# Smarttree_BMS_6.net
KiCad netlist of a schematic drawn in EAGLE
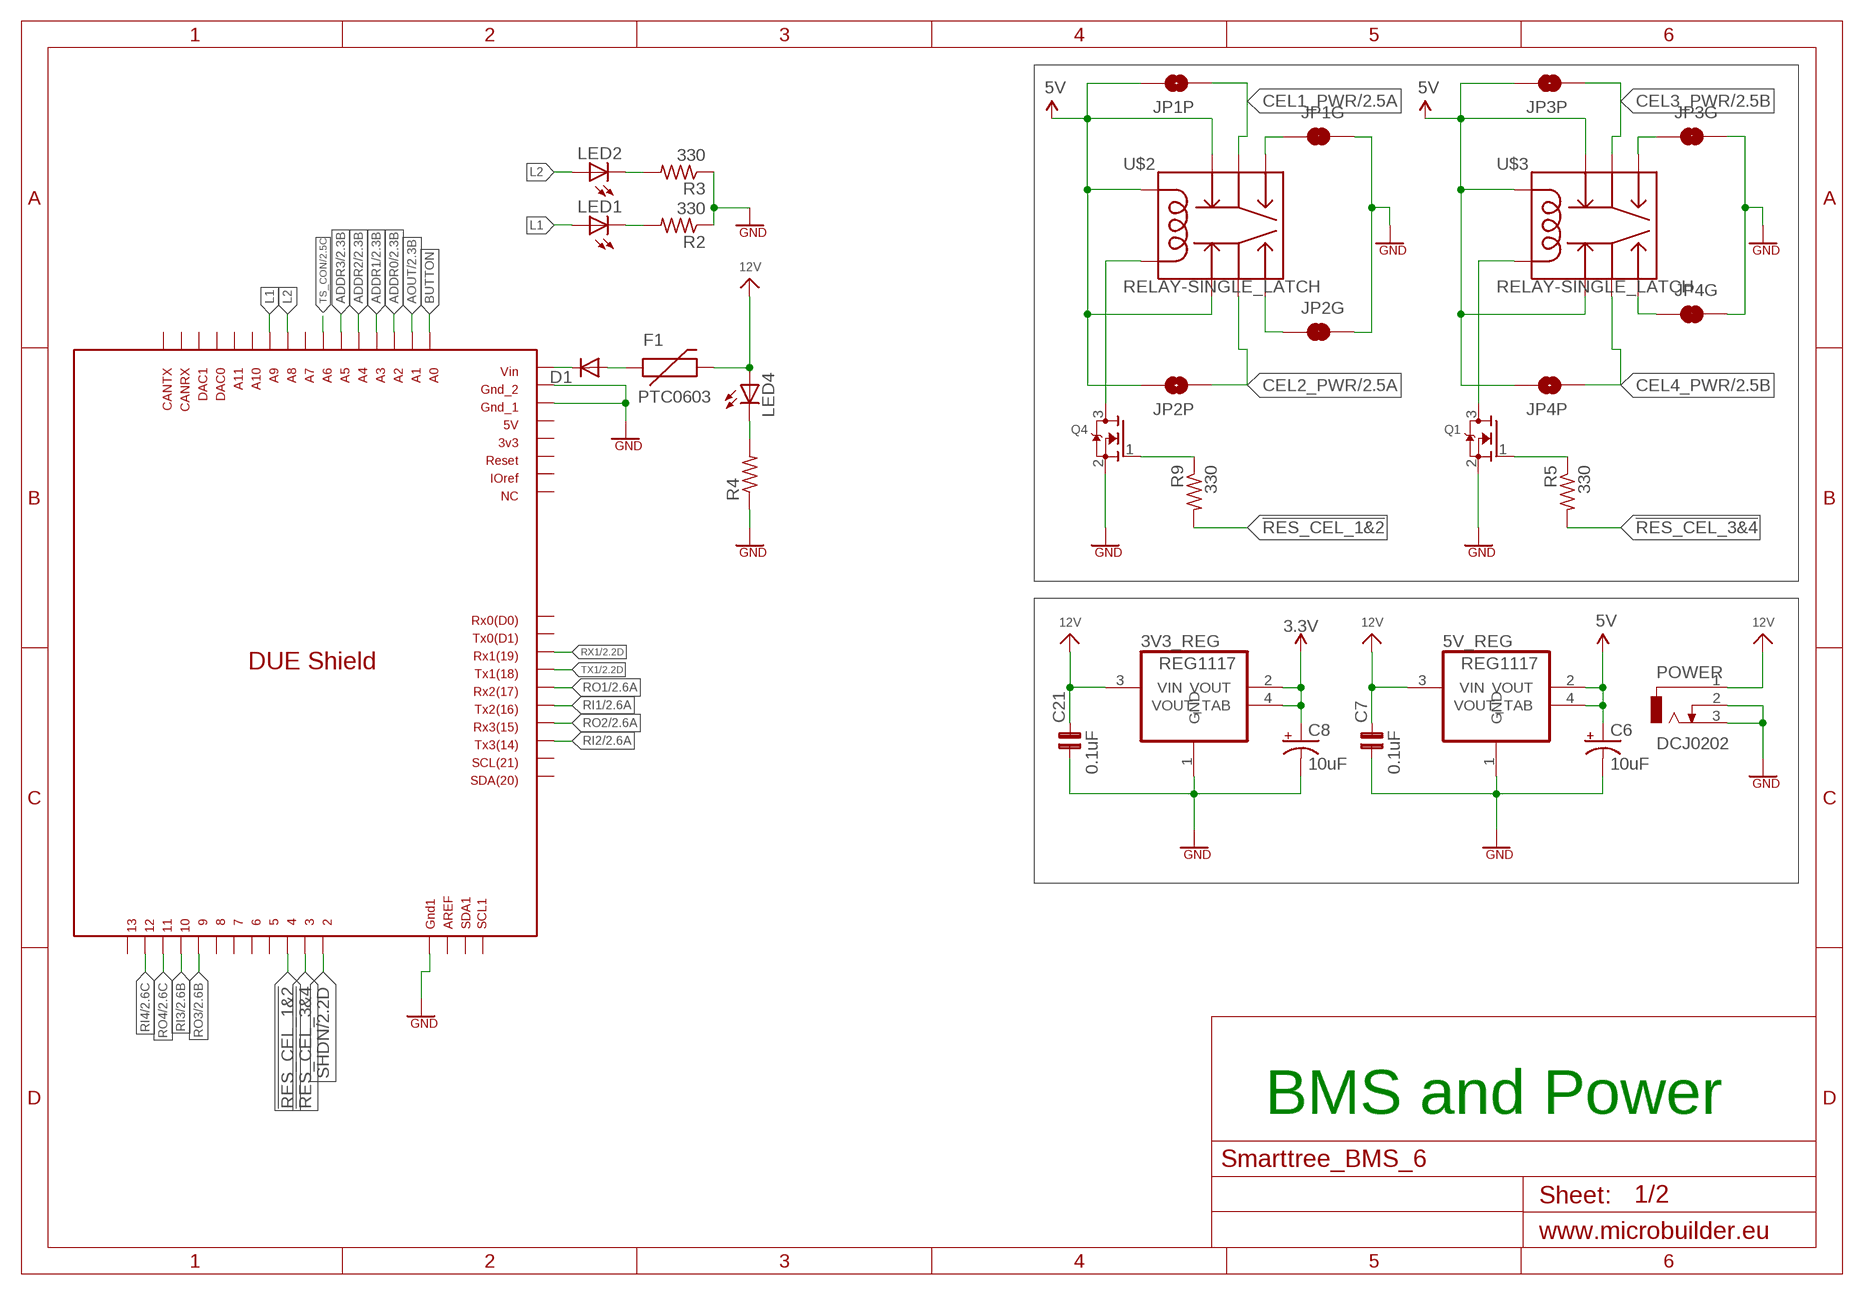
[diagram p0: schematic, sheet 1]
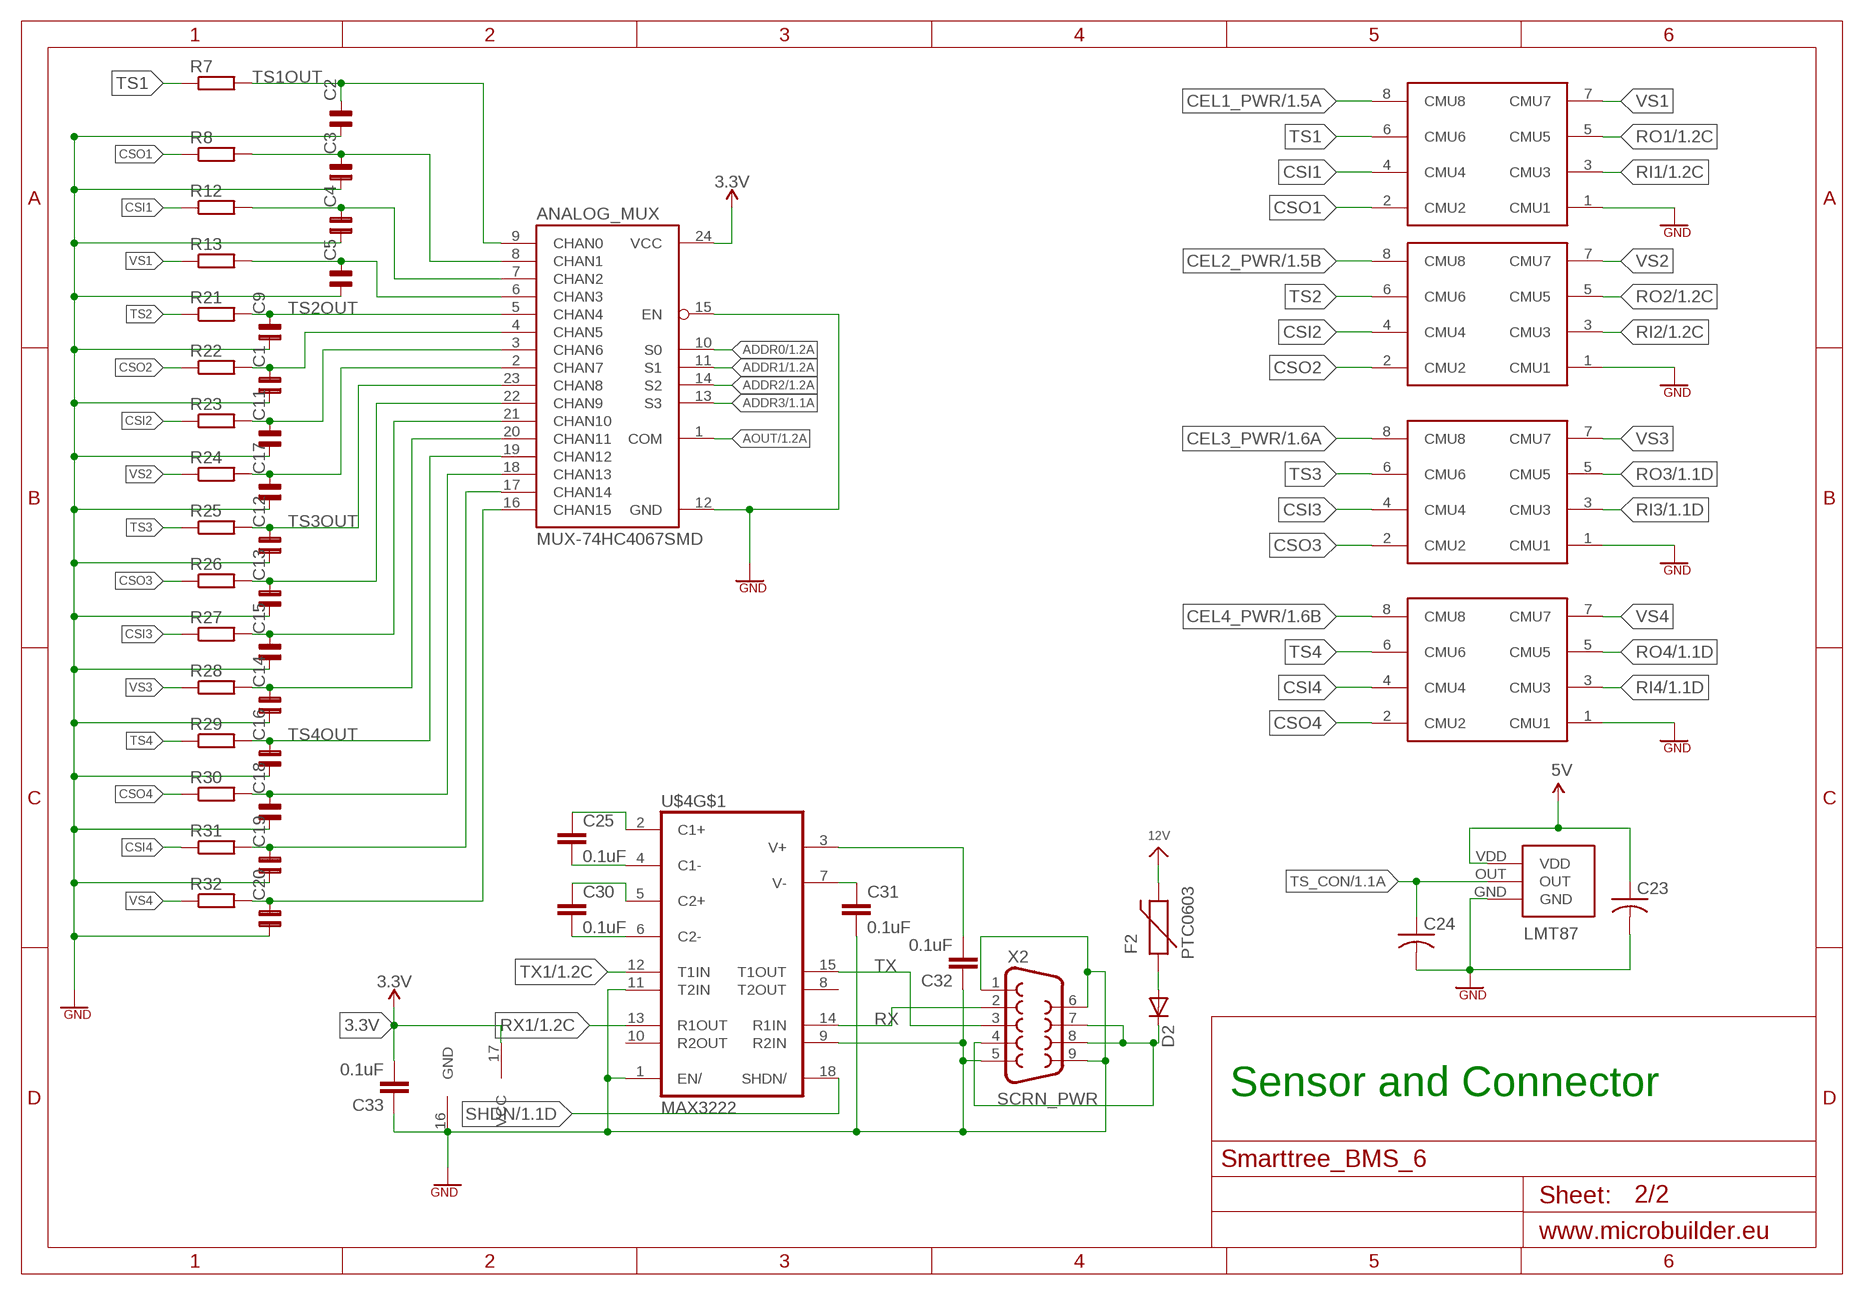
[diagram p1: schematic, sheet 2]

(export (version "E")
  (design (tool "Eeschema 10.0.6"))
  (components
    (comp (ref "3V3_REG")
      (value "REG1117")
      (footprint "eagle-import:SOT223")
      (libsource (lib "eagle-import") (part "REG1117"))
    )
    (comp (ref "5V_REG")
      (value "REG1117")
      (footprint "eagle-import:SOT223")
      (libsource (lib "eagle-import") (part "REG1117"))
    )
    (comp (ref "C6")
      (value "10uF")
      (footprint "eagle-import:EIA3216")
      (libsource (lib "eagle-import") (part "10UF-TANT"))
    )
    (comp (ref "C7")
      (value "0.1uF")
      (footprint "eagle-import:C-0805")
      (libsource (lib "eagle-import") (part "C-NP-SMD-0805"))
    )
    (comp (ref "C8")
      (value "10uF")
      (footprint "eagle-import:EIA3216")
      (libsource (lib "eagle-import") (part "10UF-TANT"))
    )
    (comp (ref "C21")
      (value "0.1uF")
      (footprint "eagle-import:C-0805")
      (libsource (lib "eagle-import") (part "C-NP-SMD-0805"))
    )
    (comp (ref "D1")
      (value "DIODE-SOD106-R")
      (footprint "eagle-import:SOD106-R")
      (libsource (lib "eagle-import") (part "DIODE-SOD106-R"))
    )
    (comp (ref "F1")
      (value "PTC0603")
      (footprint "eagle-import:0603")
      (libsource (lib "eagle-import") (part "PTC0603"))
    )
    (comp (ref "JP1G")
      (value "JUMPER-SMT_2_NC_TRACE_SILK")
      (footprint "eagle-import:SMT-JUMPER_2_NC_TRACE_SILK")
      (libsource (lib "eagle-import") (part "JUMPER-SMT_2_NC_TRACE_SILK"))
    )
    (comp (ref "JP1P")
      (value "JUMPER-SMT_2_NO_SILK")
      (footprint "eagle-import:SMT-JUMPER_2_NO_SILK")
      (libsource (lib "eagle-import") (part "JUMPER-SMT_2_NO_SILK"))
    )
    (comp (ref "JP2G")
      (value "JUMPER-SMT_2_NC_TRACE_SILK")
      (footprint "eagle-import:SMT-JUMPER_2_NC_TRACE_SILK")
      (libsource (lib "eagle-import") (part "JUMPER-SMT_2_NC_TRACE_SILK"))
    )
    (comp (ref "JP2P")
      (value "JUMPER-SMT_2_NO_SILK")
      (footprint "eagle-import:SMT-JUMPER_2_NO_SILK")
      (libsource (lib "eagle-import") (part "JUMPER-SMT_2_NO_SILK"))
    )
    (comp (ref "JP3G")
      (value "JUMPER-SMT_2_NC_TRACE_SILK")
      (footprint "eagle-import:SMT-JUMPER_2_NC_TRACE_SILK")
      (libsource (lib "eagle-import") (part "JUMPER-SMT_2_NC_TRACE_SILK"))
    )
    (comp (ref "JP3P")
      (value "JUMPER-SMT_2_NO_SILK")
      (footprint "eagle-import:SMT-JUMPER_2_NO_SILK")
      (libsource (lib "eagle-import") (part "JUMPER-SMT_2_NO_SILK"))
    )
    (comp (ref "JP4G")
      (value "JUMPER-SMT_2_NC_TRACE_SILK")
      (footprint "eagle-import:SMT-JUMPER_2_NC_TRACE_SILK")
      (libsource (lib "eagle-import") (part "JUMPER-SMT_2_NC_TRACE_SILK"))
    )
    (comp (ref "JP4P")
      (value "JUMPER-SMT_2_NO_SILK")
      (footprint "eagle-import:SMT-JUMPER_2_NO_SILK")
      (libsource (lib "eagle-import") (part "JUMPER-SMT_2_NO_SILK"))
    )
    (comp (ref "LED1")
      (value "LED-YELLOW0603")
      (footprint "eagle-import:LED-0603")
      (libsource (lib "eagle-import") (part "LED-YELLOW0603"))
    )
    (comp (ref "LED2")
      (value "LED-YELLOW0603")
      (footprint "eagle-import:LED-0603")
      (libsource (lib "eagle-import") (part "LED-YELLOW0603"))
    )
    (comp (ref "LED4")
      (value "LED-YELLOW0603")
      (footprint "eagle-import:LED-0603")
      (libsource (lib "eagle-import") (part "LED-YELLOW0603"))
    )
    (comp (ref "POWER")
      (value "DCJ0202")
      (footprint "eagle-import:DCJ0202")
      (libsource (lib "eagle-import") (part "DCJ0202"))
    )
    (comp (ref "Q1")
      (value "MOSFET-NREFLOW")
      (footprint "eagle-import:SOT23")
      (libsource (lib "eagle-import") (part "MOSFET-NREFLOW"))
    )
    (comp (ref "Q4")
      (value "MOSFET-NREFLOW")
      (footprint "eagle-import:SOT23")
      (libsource (lib "eagle-import") (part "MOSFET-NREFLOW"))
    )
    (comp (ref "R2")
      (value "330")
      (footprint "eagle-import:M0805")
      (libsource (lib "eagle-import") (part "R-US_M0805"))
    )
    (comp (ref "R3")
      (value "330")
      (footprint "eagle-import:M0805")
      (libsource (lib "eagle-import") (part "R-US_M0805"))
    )
    (comp (ref "R4")
      (value "R-US_M0805")
      (footprint "eagle-import:M0805")
      (libsource (lib "eagle-import") (part "R-US_M0805"))
    )
    (comp (ref "R5")
      (value "330")
      (footprint "eagle-import:R0805")
      (libsource (lib "eagle-import") (part "R-US_R0805"))
    )
    (comp (ref "R9")
      (value "330")
      (footprint "eagle-import:R0805")
      (libsource (lib "eagle-import") (part "R-US_R0805"))
    )
    (comp (ref "U$1")
      (value "DUE(OUTLINE)")
      (footprint "eagle-import:DUE(NORMAL)")
      (libsource (lib "eagle-import") (part "DUE(OUTLINE)"))
    )
    (comp (ref "U$2")
      (value "RELAY-SINGLE_LATCH")
      (footprint "eagle-import:RELAY-EE2")
      (libsource (lib "eagle-import") (part "RELAY-SINGLE_LATCH"))
    )
    (comp (ref "U$3")
      (value "RELAY-SINGLE_LATCH")
      (footprint "eagle-import:RELAY-EE2")
      (libsource (lib "eagle-import") (part "RELAY-SINGLE_LATCH"))
    )
    (comp (ref "ANALOG_MUX")
      (value "MUX-74HC4067SMD")
      (footprint "eagle-import:SSOP24")
      (libsource (lib "eagle-import") (part "MUX-74HC4067SMD"))
    )
    (comp (ref "C1")
      (value "C-NP-SMD-0805")
      (footprint "eagle-import:C-0805")
      (libsource (lib "eagle-import") (part "C-NP-SMD-0805"))
    )
    (comp (ref "C2")
      (value "C-NP-SMD-0805")
      (footprint "eagle-import:C-0805")
      (libsource (lib "eagle-import") (part "C-NP-SMD-0805"))
    )
    (comp (ref "C3")
      (value "C-NP-SMD-0805")
      (footprint "eagle-import:C-0805")
      (libsource (lib "eagle-import") (part "C-NP-SMD-0805"))
    )
    (comp (ref "C4")
      (value "C-NP-SMD-0805")
      (footprint "eagle-import:C-0805")
      (libsource (lib "eagle-import") (part "C-NP-SMD-0805"))
    )
    (comp (ref "C5")
      (value "C-NP-SMD-0805")
      (footprint "eagle-import:C-0805")
      (libsource (lib "eagle-import") (part "C-NP-SMD-0805"))
    )
    (comp (ref "C9")
      (value "C-NP-SMD-0805")
      (footprint "eagle-import:C-0805")
      (libsource (lib "eagle-import") (part "C-NP-SMD-0805"))
    )
    (comp (ref "C11")
      (value "C-NP-SMD-0805")
      (footprint "eagle-import:C-0805")
      (libsource (lib "eagle-import") (part "C-NP-SMD-0805"))
    )
    (comp (ref "C12")
      (value "C-NP-SMD-0805")
      (footprint "eagle-import:C-0805")
      (libsource (lib "eagle-import") (part "C-NP-SMD-0805"))
    )
    (comp (ref "C13")
      (value "C-NP-SMD-0805")
      (footprint "eagle-import:C-0805")
      (libsource (lib "eagle-import") (part "C-NP-SMD-0805"))
    )
    (comp (ref "C14")
      (value "C-NP-SMD-0805")
      (footprint "eagle-import:C-0805")
      (libsource (lib "eagle-import") (part "C-NP-SMD-0805"))
    )
    (comp (ref "C15")
      (value "C-NP-SMD-0805")
      (footprint "eagle-import:C-0805")
      (libsource (lib "eagle-import") (part "C-NP-SMD-0805"))
    )
    (comp (ref "C16")
      (value "C-NP-SMD-0805")
      (footprint "eagle-import:C-0805")
      (libsource (lib "eagle-import") (part "C-NP-SMD-0805"))
    )
    (comp (ref "C17")
      (value "C-NP-SMD-0805")
      (footprint "eagle-import:C-0805")
      (libsource (lib "eagle-import") (part "C-NP-SMD-0805"))
    )
    (comp (ref "C18")
      (value "C-NP-SMD-0805")
      (footprint "eagle-import:C-0805")
      (libsource (lib "eagle-import") (part "C-NP-SMD-0805"))
    )
    (comp (ref "C19")
      (value "C-NP-SMD-0805")
      (footprint "eagle-import:C-0805")
      (libsource (lib "eagle-import") (part "C-NP-SMD-0805"))
    )
    (comp (ref "C20")
      (value "C-NP-SMD-0805")
      (footprint "eagle-import:C-0805")
      (libsource (lib "eagle-import") (part "C-NP-SMD-0805"))
    )
    (comp (ref "C23")
      (value "C-USC0805")
      (footprint "eagle-import:C0805")
      (libsource (lib "eagle-import") (part "C-USC0805"))
    )
    (comp (ref "C24")
      (value "C-USC0805")
      (footprint "eagle-import:C0805")
      (libsource (lib "eagle-import") (part "C-USC0805"))
    )
    (comp (ref "C25")
      (value "0.1uF")
      (footprint "eagle-import:0603-CAP")
      (libsource (lib "eagle-import") (part "CAP0603-CAP"))
    )
    (comp (ref "C30")
      (value "0.1uF")
      (footprint "eagle-import:0603-CAP")
      (libsource (lib "eagle-import") (part "CAP0603-CAP"))
    )
    (comp (ref "C31")
      (value "0.1uF")
      (footprint "eagle-import:0603-CAP")
      (libsource (lib "eagle-import") (part "CAP0603-CAP"))
    )
    (comp (ref "C32")
      (value "0.1uF")
      (footprint "eagle-import:0603-CAP")
      (libsource (lib "eagle-import") (part "CAP0603-CAP"))
    )
    (comp (ref "C33")
      (value "0.1uF")
      (footprint "eagle-import:0603-CAP")
      (libsource (lib "eagle-import") (part "CAP0603-CAP"))
    )
    (comp (ref "CEL1")
      (value "8PINCONN")
      (footprint "eagle-import:8PINCONN")
      (libsource (lib "eagle-import") (part "8PINCONN"))
    )
    (comp (ref "CEL2")
      (value "8PINCONN")
      (footprint "eagle-import:8PINCONN")
      (libsource (lib "eagle-import") (part "8PINCONN"))
    )
    (comp (ref "CEL3")
      (value "8PINCONN")
      (footprint "eagle-import:8PINCONN")
      (libsource (lib "eagle-import") (part "8PINCONN"))
    )
    (comp (ref "CEL4")
      (value "8PINCONN")
      (footprint "eagle-import:8PINCONN")
      (libsource (lib "eagle-import") (part "8PINCONN"))
    )
    (comp (ref "D2")
      (value "DIODE-SOD106-R")
      (footprint "eagle-import:SOD106-R")
      (libsource (lib "eagle-import") (part "DIODE-SOD106-R"))
    )
    (comp (ref "F2")
      (value "PTC0603")
      (footprint "eagle-import:0603")
      (libsource (lib "eagle-import") (part "PTC0603"))
    )
    (comp (ref "LMT87")
      (value "LMT87_PAC")
      (footprint "eagle-import:LMT87_TO")
      (libsource (lib "eagle-import") (part "LMT87_PAC"))
    )
    (comp (ref "R7")
      (value "R-EU_R0805W")
      (footprint "eagle-import:R0805W")
      (libsource (lib "eagle-import") (part "R-EU_R0805W"))
    )
    (comp (ref "R8")
      (value "R-EU_R0805W")
      (footprint "eagle-import:R0805W")
      (libsource (lib "eagle-import") (part "R-EU_R0805W"))
    )
    (comp (ref "R12")
      (value "R-EU_R0805W")
      (footprint "eagle-import:R0805W")
      (libsource (lib "eagle-import") (part "R-EU_R0805W"))
    )
    (comp (ref "R13")
      (value "R-EU_R0805W")
      (footprint "eagle-import:R0805W")
      (libsource (lib "eagle-import") (part "R-EU_R0805W"))
    )
    (comp (ref "R21")
      (value "R-EU_R0805W")
      (footprint "eagle-import:R0805W")
      (libsource (lib "eagle-import") (part "R-EU_R0805W"))
    )
    (comp (ref "R22")
      (value "R-EU_R0805W")
      (footprint "eagle-import:R0805W")
      (libsource (lib "eagle-import") (part "R-EU_R0805W"))
    )
    (comp (ref "R23")
      (value "R-EU_R0805W")
      (footprint "eagle-import:R0805W")
      (libsource (lib "eagle-import") (part "R-EU_R0805W"))
    )
    (comp (ref "R24")
      (value "R-EU_R0805W")
      (footprint "eagle-import:R0805W")
      (libsource (lib "eagle-import") (part "R-EU_R0805W"))
    )
    (comp (ref "R25")
      (value "R-EU_R0805W")
      (footprint "eagle-import:R0805W")
      (libsource (lib "eagle-import") (part "R-EU_R0805W"))
    )
    (comp (ref "R26")
      (value "R-EU_R0805W")
      (footprint "eagle-import:R0805W")
      (libsource (lib "eagle-import") (part "R-EU_R0805W"))
    )
    (comp (ref "R27")
      (value "R-EU_R0805W")
      (footprint "eagle-import:R0805W")
      (libsource (lib "eagle-import") (part "R-EU_R0805W"))
    )
    (comp (ref "R28")
      (value "R-EU_R0805W")
      (footprint "eagle-import:R0805W")
      (libsource (lib "eagle-import") (part "R-EU_R0805W"))
    )
    (comp (ref "R29")
      (value "R-EU_R0805W")
      (footprint "eagle-import:R0805W")
      (libsource (lib "eagle-import") (part "R-EU_R0805W"))
    )
    (comp (ref "R30")
      (value "R-EU_R0805W")
      (footprint "eagle-import:R0805W")
      (libsource (lib "eagle-import") (part "R-EU_R0805W"))
    )
    (comp (ref "R31")
      (value "R-EU_R0805W")
      (footprint "eagle-import:R0805W")
      (libsource (lib "eagle-import") (part "R-EU_R0805W"))
    )
    (comp (ref "R32")
      (value "R-EU_R0805W")
      (footprint "eagle-import:R0805W")
      (libsource (lib "eagle-import") (part "R-EU_R0805W"))
    )
    (comp (ref "U$4")
      (value "MAX3222")
      (footprint "eagle-import:SO18")
      (libsource (lib "eagle-import") (part "MAX3222"))
    )
    (comp (ref "X2")
      (value "DB9MALE")
      (footprint "eagle-import:DB9_MALE")
      (libsource (lib "eagle-import") (part "DB9MALE"))
    )
  )
  (nets
    (net (code "1") (name "3.3V") (class "Default")
      (node (ref "3V3_REG") (pin "2") (pinfunction "VOUT_2") (pintype "output"))
      (node (ref "3V3_REG") (pin "4") (pinfunction "VOUT_TAB_4") (pintype "bidirectional"))
      (node (ref "ANALOG_MUX") (pin "24") (pinfunction "VCC_24") (pintype "bidirectional"))
      (node (ref "C33") (pin "2") (pinfunction "2_2") (pintype "passive"))
      (node (ref "C8") (pin "A") (pinfunction "+_A") (pintype "passive"))
      (node (ref "U$4") (pin "17") (pinfunction "VCC_17") (pintype "bidirectional"))
    )
    (net (code "2") (name "5V") (class "Default")
      (node (ref "5V_REG") (pin "2") (pinfunction "VOUT_2") (pintype "output"))
      (node (ref "5V_REG") (pin "4") (pinfunction "VOUT_TAB_4") (pintype "bidirectional"))
      (node (ref "C23") (pin "1") (pinfunction "1_1") (pintype "passive"))
      (node (ref "C6") (pin "A") (pinfunction "+_A") (pintype "passive"))
      (node (ref "JP1P") (pin "2") (pinfunction "2_2") (pintype "passive"))
      (node (ref "JP2P") (pin "2") (pinfunction "2_2") (pintype "passive"))
      (node (ref "JP3P") (pin "2") (pinfunction "2_2") (pintype "passive"))
      (node (ref "JP4P") (pin "2") (pinfunction "2_2") (pintype "passive"))
      (node (ref "LMT87") (pin "VDD") (pinfunction "VDD_VDD") (pintype "bidirectional"))
      (node (ref "U$2") (pin "P$1") (pinfunction "COIL1_P$1") (pintype "bidirectional"))
      (node (ref "U$2") (pin "P$10") (pinfunction "P$10_P$10") (pintype "bidirectional"))
      (node (ref "U$2") (pin "P$3") (pinfunction "P$3_P$3") (pintype "bidirectional"))
      (node (ref "U$3") (pin "P$1") (pinfunction "COIL1_P$1") (pintype "bidirectional"))
      (node (ref "U$3") (pin "P$10") (pinfunction "P$10_P$10") (pintype "bidirectional"))
      (node (ref "U$3") (pin "P$3") (pinfunction "P$3_P$3") (pintype "bidirectional"))
    )
    (net (code "3") (name "12V") (class "Default")
      (node (ref "3V3_REG") (pin "3") (pinfunction "VIN_3") (pintype "input"))
      (node (ref "5V_REG") (pin "3") (pinfunction "VIN_3") (pintype "input"))
      (node (ref "C21") (pin "2") (pinfunction "2_2") (pintype "passive"))
      (node (ref "C7") (pin "2") (pinfunction "2_2") (pintype "passive"))
      (node (ref "F1") (pin "2") (pinfunction "2_2") (pintype "bidirectional"))
      (node (ref "F2") (pin "2") (pinfunction "2_2") (pintype "bidirectional"))
      (node (ref "LED4") (pin "A") (pinfunction "A_A") (pintype "passive"))
      (node (ref "POWER") (pin "1") (pinfunction "1_1") (pintype "passive"))
    )
    (net (code "4") (name "ADDR0") (class "Default")
      (node (ref "ANALOG_MUX") (pin "10") (pinfunction "S0_10") (pintype "input"))
      (node (ref "U$1") (pin "A2") (pinfunction "A2_A2") (pintype "bidirectional"))
    )
    (net (code "5") (name "ADDR1") (class "Default")
      (node (ref "ANALOG_MUX") (pin "11") (pinfunction "S1_11") (pintype "input"))
      (node (ref "U$1") (pin "A3") (pinfunction "A3_A3") (pintype "bidirectional"))
    )
    (net (code "6") (name "ADDR2") (class "Default")
      (node (ref "ANALOG_MUX") (pin "14") (pinfunction "S2_14") (pintype "input"))
      (node (ref "U$1") (pin "A4") (pinfunction "A4_A4") (pintype "bidirectional"))
    )
    (net (code "7") (name "ADDR3") (class "Default")
      (node (ref "ANALOG_MUX") (pin "13") (pinfunction "S3_13") (pintype "input"))
      (node (ref "U$1") (pin "A5") (pinfunction "A5_A5") (pintype "bidirectional"))
    )
    (net (code "8") (name "AOUT") (class "Default")
      (node (ref "ANALOG_MUX") (pin "1") (pinfunction "COM_1") (pintype "bidirectional"))
      (node (ref "U$1") (pin "A1") (pinfunction "A1_A1") (pintype "bidirectional"))
    )
    (net (code "9") (name "BUTTON") (class "Default")
      (node (ref "U$1") (pin "A0") (pinfunction "A0_A0") (pintype "bidirectional"))
    )
    (net (code "10") (name "CEL1_PWR") (class "Default")
      (node (ref "CEL1") (pin "8") (pinfunction "CMU8_8") (pintype "bidirectional"))
      (node (ref "JP1P") (pin "1") (pinfunction "1_1") (pintype "passive"))
      (node (ref "U$2") (pin "P$4") (pinfunction "P$4_P$4") (pintype "bidirectional"))
    )
    (net (code "11") (name "CEL2_PWR") (class "Default")
      (node (ref "CEL2") (pin "8") (pinfunction "CMU8_8") (pintype "bidirectional"))
      (node (ref "JP2P") (pin "1") (pinfunction "1_1") (pintype "passive"))
      (node (ref "U$2") (pin "P$9") (pinfunction "P$9_P$9") (pintype "bidirectional"))
    )
    (net (code "12") (name "CEL3_PWR") (class "Default")
      (node (ref "CEL3") (pin "8") (pinfunction "CMU8_8") (pintype "bidirectional"))
      (node (ref "JP3P") (pin "1") (pinfunction "1_1") (pintype "passive"))
      (node (ref "U$3") (pin "P$4") (pinfunction "P$4_P$4") (pintype "bidirectional"))
    )
    (net (code "13") (name "CEL4_PWR") (class "Default")
      (node (ref "CEL4") (pin "8") (pinfunction "CMU8_8") (pintype "bidirectional"))
      (node (ref "JP4P") (pin "1") (pinfunction "1_1") (pintype "passive"))
      (node (ref "U$3") (pin "P$9") (pinfunction "P$9_P$9") (pintype "bidirectional"))
    )
    (net (code "14") (name "CSI1") (class "Default")
      (node (ref "CEL1") (pin "4") (pinfunction "CMU4_4") (pintype "bidirectional"))
      (node (ref "R12") (pin "1") (pinfunction "1_1") (pintype "passive"))
    )
    (net (code "15") (name "CSI2") (class "Default")
      (node (ref "CEL2") (pin "4") (pinfunction "CMU4_4") (pintype "bidirectional"))
      (node (ref "R23") (pin "1") (pinfunction "1_1") (pintype "passive"))
    )
    (net (code "16") (name "CSI3") (class "Default")
      (node (ref "CEL3") (pin "4") (pinfunction "CMU4_4") (pintype "bidirectional"))
      (node (ref "R27") (pin "1") (pinfunction "1_1") (pintype "passive"))
    )
    (net (code "17") (name "CSI4") (class "Default")
      (node (ref "CEL4") (pin "4") (pinfunction "CMU4_4") (pintype "bidirectional"))
      (node (ref "R31") (pin "1") (pinfunction "1_1") (pintype "passive"))
    )
    (net (code "18") (name "CSO1") (class "Default")
      (node (ref "CEL1") (pin "2") (pinfunction "CMU2_2") (pintype "bidirectional"))
      (node (ref "R8") (pin "1") (pinfunction "1_1") (pintype "passive"))
    )
    (net (code "19") (name "CSO2") (class "Default")
      (node (ref "CEL2") (pin "2") (pinfunction "CMU2_2") (pintype "bidirectional"))
      (node (ref "R22") (pin "1") (pinfunction "1_1") (pintype "passive"))
    )
    (net (code "20") (name "CSO3") (class "Default")
      (node (ref "CEL3") (pin "2") (pinfunction "CMU2_2") (pintype "bidirectional"))
      (node (ref "R26") (pin "1") (pinfunction "1_1") (pintype "passive"))
    )
    (net (code "21") (name "CSO4") (class "Default")
      (node (ref "CEL4") (pin "2") (pinfunction "CMU2_2") (pintype "bidirectional"))
      (node (ref "R30") (pin "1") (pinfunction "1_1") (pintype "passive"))
    )
    (net (code "22") (name "GND") (class "Default")
      (node (ref "3V3_REG") (pin "1") (pinfunction "GND_1") (pintype "power_in"))
      (node (ref "5V_REG") (pin "1") (pinfunction "GND_1") (pintype "power_in"))
      (node (ref "ANALOG_MUX") (pin "12") (pinfunction "GND_12") (pintype "bidirectional"))
      (node (ref "ANALOG_MUX") (pin "15") (pinfunction "EN_15") (pintype "input"))
      (node (ref "C1") (pin "1") (pinfunction "1_1") (pintype "passive"))
      (node (ref "C11") (pin "1") (pinfunction "1_1") (pintype "passive"))
      (node (ref "C12") (pin "1") (pinfunction "1_1") (pintype "passive"))
      (node (ref "C13") (pin "1") (pinfunction "1_1") (pintype "passive"))
      (node (ref "C14") (pin "1") (pinfunction "1_1") (pintype "passive"))
      (node (ref "C15") (pin "1") (pinfunction "1_1") (pintype "passive"))
      (node (ref "C16") (pin "1") (pinfunction "1_1") (pintype "passive"))
      (node (ref "C17") (pin "1") (pinfunction "1_1") (pintype "passive"))
      (node (ref "C18") (pin "1") (pinfunction "1_1") (pintype "passive"))
      (node (ref "C19") (pin "1") (pinfunction "1_1") (pintype "passive"))
      (node (ref "C2") (pin "1") (pinfunction "1_1") (pintype "passive"))
      (node (ref "C20") (pin "1") (pinfunction "1_1") (pintype "passive"))
      (node (ref "C21") (pin "1") (pinfunction "1_1") (pintype "passive"))
      (node (ref "C23") (pin "2") (pinfunction "2_2") (pintype "passive"))
      (node (ref "C24") (pin "2") (pinfunction "2_2") (pintype "passive"))
      (node (ref "C3") (pin "1") (pinfunction "1_1") (pintype "passive"))
      (node (ref "C31") (pin "2") (pinfunction "2_2") (pintype "passive"))
      (node (ref "C32") (pin "1") (pinfunction "1_1") (pintype "passive"))
      (node (ref "C33") (pin "1") (pinfunction "1_1") (pintype "passive"))
      (node (ref "C4") (pin "1") (pinfunction "1_1") (pintype "passive"))
      (node (ref "C5") (pin "1") (pinfunction "1_1") (pintype "passive"))
      (node (ref "C6") (pin "C") (pinfunction "-_C") (pintype "passive"))
      (node (ref "C7") (pin "1") (pinfunction "1_1") (pintype "passive"))
      (node (ref "C8") (pin "C") (pinfunction "-_C") (pintype "passive"))
      (node (ref "C9") (pin "1") (pinfunction "1_1") (pintype "passive"))
      (node (ref "CEL1") (pin "1") (pinfunction "CMU1_1") (pintype "bidirectional"))
      (node (ref "CEL2") (pin "1") (pinfunction "CMU1_1") (pintype "bidirectional"))
      (node (ref "CEL3") (pin "1") (pinfunction "CMU1_1") (pintype "bidirectional"))
      (node (ref "CEL4") (pin "1") (pinfunction "CMU1_1") (pintype "bidirectional"))
      (node (ref "JP1G") (pin "2") (pinfunction "2_2") (pintype "passive"))
      (node (ref "JP2G") (pin "2") (pinfunction "2_2") (pintype "passive"))
      (node (ref "JP3G") (pin "2") (pinfunction "2_2") (pintype "passive"))
      (node (ref "JP4G") (pin "2") (pinfunction "2_2") (pintype "passive"))
      (node (ref "LMT87") (pin "GND") (pinfunction "GND_GND") (pintype "bidirectional"))
      (node (ref "POWER") (pin "2") (pinfunction "2_2") (pintype "passive"))
      (node (ref "POWER") (pin "3") (pinfunction "3_3") (pintype "passive"))
      (node (ref "Q1") (pin "2") (pinfunction "S_2") (pintype "bidirectional"))
      (node (ref "Q4") (pin "2") (pinfunction "S_2") (pintype "bidirectional"))
      (node (ref "R2") (pin "1") (pinfunction "1_1") (pintype "passive"))
      (node (ref "R3") (pin "1") (pinfunction "1_1") (pintype "passive"))
      (node (ref "R4") (pin "1") (pinfunction "1_1") (pintype "passive"))
      (node (ref "U$1") (pin "GND1") (pinfunction "GND1_GND1") (pintype "bidirectional"))
      (node (ref "U$1") (pin "GND_1") (pinfunction "GND_1_GND_1") (pintype "bidirectional"))
      (node (ref "U$1") (pin "GND_2") (pinfunction "GND_2_GND_2") (pintype "bidirectional"))
      (node (ref "U$4") (pin "1") (pinfunction "EN/_1") (pintype "input"))
      (node (ref "U$4") (pin "11") (pinfunction "T2IN_11") (pintype "input"))
      (node (ref "U$4") (pin "16") (pinfunction "GND_16") (pintype "bidirectional"))
      (node (ref "U$4") (pin "9") (pinfunction "R2IN_9") (pintype "input"))
      (node (ref "X2") (pin "1") (pinfunction "1_1") (pintype "passive"))
      (node (ref "X2") (pin "5") (pinfunction "5_5") (pintype "passive"))
      (node (ref "X2") (pin "6") (pinfunction "6_6") (pintype "passive"))
      (node (ref "X2") (pin "9") (pinfunction "9_9") (pintype "passive"))
    )
    (net (code "23") (name "L1") (class "Default")
      (node (ref "LED1") (pin "A") (pinfunction "A_A") (pintype "passive"))
      (node (ref "U$1") (pin "A9") (pinfunction "A9_A9") (pintype "bidirectional"))
    )
    (net (code "24") (name "L2") (class "Default")
      (node (ref "LED2") (pin "A") (pinfunction "A_A") (pintype "passive"))
      (node (ref "U$1") (pin "A8") (pinfunction "A8_A8") (pintype "bidirectional"))
    )
    (net (code "25") (name "Net-(ANALOG_MUX-CHAN1)") (class "Default")
      (node (ref "ANALOG_MUX") (pin "8") (pinfunction "CHAN1_8") (pintype "bidirectional"))
      (node (ref "C3") (pin "2") (pinfunction "2_2") (pintype "passive"))
      (node (ref "R8") (pin "2") (pinfunction "2_2") (pintype "passive"))
    )
    (net (code "26") (name "Net-(ANALOG_MUX-CHAN2)") (class "Default")
      (node (ref "ANALOG_MUX") (pin "7") (pinfunction "CHAN2_7") (pintype "bidirectional"))
      (node (ref "C4") (pin "2") (pinfunction "2_2") (pintype "passive"))
      (node (ref "R12") (pin "2") (pinfunction "2_2") (pintype "passive"))
    )
    (net (code "27") (name "Net-(ANALOG_MUX-CHAN3)") (class "Default")
      (node (ref "ANALOG_MUX") (pin "6") (pinfunction "CHAN3_6") (pintype "bidirectional"))
      (node (ref "C5") (pin "2") (pinfunction "2_2") (pintype "passive"))
      (node (ref "R13") (pin "2") (pinfunction "2_2") (pintype "passive"))
    )
    (net (code "28") (name "Net-(ANALOG_MUX-CHAN5)") (class "Default")
      (node (ref "ANALOG_MUX") (pin "4") (pinfunction "CHAN5_4") (pintype "bidirectional"))
      (node (ref "C1") (pin "2") (pinfunction "2_2") (pintype "passive"))
      (node (ref "R22") (pin "2") (pinfunction "2_2") (pintype "passive"))
    )
    (net (code "29") (name "Net-(ANALOG_MUX-CHAN6)") (class "Default")
      (node (ref "ANALOG_MUX") (pin "3") (pinfunction "CHAN6_3") (pintype "bidirectional"))
      (node (ref "C11") (pin "2") (pinfunction "2_2") (pintype "passive"))
      (node (ref "R23") (pin "2") (pinfunction "2_2") (pintype "passive"))
    )
    (net (code "30") (name "Net-(ANALOG_MUX-CHAN7)") (class "Default")
      (node (ref "ANALOG_MUX") (pin "2") (pinfunction "CHAN7_2") (pintype "bidirectional"))
      (node (ref "C17") (pin "2") (pinfunction "2_2") (pintype "passive"))
      (node (ref "R24") (pin "2") (pinfunction "2_2") (pintype "passive"))
    )
    (net (code "31") (name "Net-(ANALOG_MUX-CHAN9)") (class "Default")
      (node (ref "ANALOG_MUX") (pin "22") (pinfunction "CHAN9_22") (pintype "bidirectional"))
      (node (ref "C13") (pin "2") (pinfunction "2_2") (pintype "passive"))
      (node (ref "R26") (pin "2") (pinfunction "2_2") (pintype "passive"))
    )
    (net (code "32") (name "Net-(ANALOG_MUX-CHAN10)") (class "Default")
      (node (ref "ANALOG_MUX") (pin "21") (pinfunction "CHAN10_21") (pintype "bidirectional"))
      (node (ref "C15") (pin "2") (pinfunction "2_2") (pintype "passive"))
      (node (ref "R27") (pin "2") (pinfunction "2_2") (pintype "passive"))
    )
    (net (code "33") (name "Net-(ANALOG_MUX-CHAN11)") (class "Default")
      (node (ref "ANALOG_MUX") (pin "20") (pinfunction "CHAN11_20") (pintype "bidirectional"))
      (node (ref "C14") (pin "2") (pinfunction "2_2") (pintype "passive"))
      (node (ref "R28") (pin "2") (pinfunction "2_2") (pintype "passive"))
    )
    (net (code "34") (name "Net-(ANALOG_MUX-CHAN13)") (class "Default")
      (node (ref "ANALOG_MUX") (pin "18") (pinfunction "CHAN13_18") (pintype "bidirectional"))
      (node (ref "C18") (pin "2") (pinfunction "2_2") (pintype "passive"))
      (node (ref "R30") (pin "2") (pinfunction "2_2") (pintype "passive"))
    )
    (net (code "35") (name "Net-(ANALOG_MUX-CHAN14)") (class "Default")
      (node (ref "ANALOG_MUX") (pin "17") (pinfunction "CHAN14_17") (pintype "bidirectional"))
      (node (ref "C19") (pin "2") (pinfunction "2_2") (pintype "passive"))
      (node (ref "R31") (pin "2") (pinfunction "2_2") (pintype "passive"))
    )
    (net (code "36") (name "Net-(ANALOG_MUX-CHAN15)") (class "Default")
      (node (ref "ANALOG_MUX") (pin "16") (pinfunction "CHAN15_16") (pintype "bidirectional"))
      (node (ref "C20") (pin "2") (pinfunction "2_2") (pintype "passive"))
      (node (ref "R32") (pin "2") (pinfunction "2_2") (pintype "passive"))
    )
    (net (code "37") (name "Net-(D1-PadA)") (class "Default")
      (node (ref "D1") (pin "A") (pinfunction "A_A") (pintype "passive"))
      (node (ref "F1") (pin "1") (pinfunction "1_1") (pintype "bidirectional"))
    )
    (net (code "38") (name "Net-(D1-PadC)") (class "Default")
      (node (ref "D1") (pin "C") (pinfunction "C_C") (pintype "passive"))
      (node (ref "U$1") (pin "VIN") (pinfunction "VIN_VIN") (pintype "bidirectional"))
    )
    (net (code "39") (name "Net-(D2-PadA)") (class "Default")
      (node (ref "D2") (pin "A") (pinfunction "A_A") (pintype "passive"))
      (node (ref "F2") (pin "1") (pinfunction "1_1") (pintype "bidirectional"))
    )
    (net (code "40") (name "Net-(JP1G-Pad1)") (class "Default")
      (node (ref "JP1G") (pin "1") (pinfunction "1_1") (pintype "passive"))
      (node (ref "U$2") (pin "P$5") (pinfunction "P$5_P$5") (pintype "bidirectional"))
    )
    (net (code "41") (name "Net-(JP2G-Pad1)") (class "Default")
      (node (ref "JP2G") (pin "1") (pinfunction "1_1") (pintype "passive"))
      (node (ref "U$2") (pin "P$8") (pinfunction "P$8_P$8") (pintype "bidirectional"))
    )
    (net (code "42") (name "Net-(JP3G-Pad1)") (class "Default")
      (node (ref "JP3G") (pin "1") (pinfunction "1_1") (pintype "passive"))
      (node (ref "U$3") (pin "P$5") (pinfunction "P$5_P$5") (pintype "bidirectional"))
    )
    (net (code "43") (name "Net-(JP4G-Pad1)") (class "Default")
      (node (ref "JP4G") (pin "1") (pinfunction "1_1") (pintype "passive"))
      (node (ref "U$3") (pin "P$8") (pinfunction "P$8_P$8") (pintype "bidirectional"))
    )
    (net (code "44") (name "Net-(LED1-PadC)") (class "Default")
      (node (ref "LED1") (pin "C") (pinfunction "C_C") (pintype "passive"))
      (node (ref "R2") (pin "2") (pinfunction "2_2") (pintype "passive"))
    )
    (net (code "45") (name "Net-(LED2-PadC)") (class "Default")
      (node (ref "LED2") (pin "C") (pinfunction "C_C") (pintype "passive"))
      (node (ref "R3") (pin "2") (pinfunction "2_2") (pintype "passive"))
    )
    (net (code "46") (name "Net-(LED4-PadC)") (class "Default")
      (node (ref "LED4") (pin "C") (pinfunction "C_C") (pintype "passive"))
      (node (ref "R4") (pin "2") (pinfunction "2_2") (pintype "passive"))
    )
    (net (code "47") (name "Net-(Q1-D)") (class "Default")
      (node (ref "Q1") (pin "3") (pinfunction "D_3") (pintype "bidirectional"))
      (node (ref "U$3") (pin "P$12") (pinfunction "COIL12_P$12") (pintype "bidirectional"))
    )
    (net (code "48") (name "Net-(Q1-G)") (class "Default")
      (node (ref "Q1") (pin "1") (pinfunction "G_1") (pintype "bidirectional"))
      (node (ref "R5") (pin "1") (pinfunction "1_1") (pintype "passive"))
    )
    (net (code "49") (name "Net-(Q4-D)") (class "Default")
      (node (ref "Q4") (pin "3") (pinfunction "D_3") (pintype "bidirectional"))
      (node (ref "U$2") (pin "P$12") (pinfunction "COIL12_P$12") (pintype "bidirectional"))
    )
    (net (code "50") (name "Net-(Q4-G)") (class "Default")
      (node (ref "Q4") (pin "1") (pinfunction "G_1") (pintype "bidirectional"))
      (node (ref "R9") (pin "1") (pinfunction "1_1") (pintype "passive"))
    )
    (net (code "51") (name "Net-(U$4A-C1+)") (class "Default")
      (node (ref "C25") (pin "1") (pinfunction "1_1") (pintype "passive"))
      (node (ref "U$4") (pin "2") (pinfunction "C1+_2") (pintype "passive"))
    )
    (net (code "52") (name "Net-(U$4A-C1-)") (class "Default")
      (node (ref "C25") (pin "2") (pinfunction "2_2") (pintype "passive"))
      (node (ref "U$4") (pin "4") (pinfunction "C1-_4") (pintype "passive"))
    )
    (net (code "53") (name "Net-(U$4A-C2+)") (class "Default")
      (node (ref "C30") (pin "1") (pinfunction "1_1") (pintype "passive"))
      (node (ref "U$4") (pin "5") (pinfunction "C2+_5") (pintype "passive"))
    )
    (net (code "54") (name "Net-(U$4A-C2-)") (class "Default")
      (node (ref "C30") (pin "2") (pinfunction "2_2") (pintype "passive"))
      (node (ref "U$4") (pin "6") (pinfunction "C2-_6") (pintype "passive"))
    )
    (net (code "55") (name "Net-(U$4A-V+)") (class "Default")
      (node (ref "C32") (pin "2") (pinfunction "2_2") (pintype "passive"))
      (node (ref "U$4") (pin "3") (pinfunction "V+_3") (pintype "passive"))
    )
    (net (code "56") (name "Net-(U$4A-V-)") (class "Default")
      (node (ref "C31") (pin "1") (pinfunction "1_1") (pintype "passive"))
      (node (ref "U$4") (pin "7") (pinfunction "V-_7") (pintype "passive"))
    )
    (net (code "57") (name "RI1") (class "Default")
      (node (ref "CEL1") (pin "3") (pinfunction "CMU3_3") (pintype "bidirectional"))
      (node (ref "U$1") (pin "TX2") (pinfunction "TX2_TX2") (pintype "bidirectional"))
    )
    (net (code "58") (name "RI2") (class "Default")
      (node (ref "CEL2") (pin "3") (pinfunction "CMU3_3") (pintype "bidirectional"))
      (node (ref "U$1") (pin "TX3") (pinfunction "TX3_TX3") (pintype "bidirectional"))
    )
    (net (code "59") (name "RI3") (class "Default")
      (node (ref "CEL3") (pin "3") (pinfunction "CMU3_3") (pintype "bidirectional"))
      (node (ref "U$1") (pin "10") (pinfunction "10_10") (pintype "bidirectional"))
    )
    (net (code "60") (name "RI4") (class "Default")
      (node (ref "CEL4") (pin "3") (pinfunction "CMU3_3") (pintype "bidirectional"))
      (node (ref "U$1") (pin "12") (pinfunction "12_12") (pintype "bidirectional"))
    )
    (net (code "61") (name "RO1") (class "Default")
      (node (ref "CEL1") (pin "5") (pinfunction "CMU5_5") (pintype "bidirectional"))
      (node (ref "U$1") (pin "RX2") (pinfunction "RX2_RX2") (pintype "bidirectional"))
    )
    (net (code "62") (name "RO2") (class "Default")
      (node (ref "CEL2") (pin "5") (pinfunction "CMU5_5") (pintype "bidirectional"))
      (node (ref "U$1") (pin "RX3") (pinfunction "RX3_RX3") (pintype "bidirectional"))
    )
    (net (code "63") (name "RO3") (class "Default")
      (node (ref "CEL3") (pin "5") (pinfunction "CMU5_5") (pintype "bidirectional"))
      (node (ref "U$1") (pin "9") (pinfunction "9_9") (pintype "bidirectional"))
    )
    (net (code "64") (name "RO4") (class "Default")
      (node (ref "CEL4") (pin "5") (pinfunction "CMU5_5") (pintype "bidirectional"))
      (node (ref "U$1") (pin "11") (pinfunction "11_11") (pintype "bidirectional"))
    )
    (net (code "65") (name "RX") (class "Default")
      (node (ref "U$4") (pin "14") (pinfunction "R1IN_14") (pintype "input"))
      (node (ref "X2") (pin "2") (pinfunction "2_2") (pintype "passive"))
    )
    (net (code "66") (name "RX1") (class "Default")
      (node (ref "U$1") (pin "RX1") (pinfunction "RX1_RX1") (pintype "bidirectional"))
      (node (ref "U$4") (pin "13") (pinfunction "R1OUT_13") (pintype "output"))
    )
    (net (code "67") (name "SCRN_PWR") (class "Default")
      (node (ref "D2") (pin "C") (pinfunction "C_C") (pintype "passive"))
      (node (ref "X2") (pin "4") (pinfunction "4_4") (pintype "passive"))
      (node (ref "X2") (pin "7") (pinfunction "7_7") (pintype "passive"))
      (node (ref "X2") (pin "8") (pinfunction "8_8") (pintype "passive"))
    )
    (net (code "68") (name "SHDN") (class "Default")
      (node (ref "U$1") (pin "2") (pinfunction "2_2") (pintype "bidirectional"))
      (node (ref "U$4") (pin "18") (pinfunction "SHDN/_18") (pintype "input"))
    )
    (net (code "69") (name "TS1") (class "Default")
      (node (ref "CEL1") (pin "6") (pinfunction "CMU6_6") (pintype "bidirectional"))
      (node (ref "R7") (pin "1") (pinfunction "1_1") (pintype "passive"))
    )
    (net (code "70") (name "TS1OUT") (class "Default")
      (node (ref "ANALOG_MUX") (pin "9") (pinfunction "CHAN0_9") (pintype "bidirectional"))
      (node (ref "C2") (pin "2") (pinfunction "2_2") (pintype "passive"))
      (node (ref "R7") (pin "2") (pinfunction "2_2") (pintype "passive"))
    )
    (net (code "71") (name "TS2") (class "Default")
      (node (ref "CEL2") (pin "6") (pinfunction "CMU6_6") (pintype "bidirectional"))
      (node (ref "R21") (pin "1") (pinfunction "1_1") (pintype "passive"))
    )
    (net (code "72") (name "TS2OUT") (class "Default")
      (node (ref "ANALOG_MUX") (pin "5") (pinfunction "CHAN4_5") (pintype "bidirectional"))
      (node (ref "C9") (pin "2") (pinfunction "2_2") (pintype "passive"))
      (node (ref "R21") (pin "2") (pinfunction "2_2") (pintype "passive"))
    )
    (net (code "73") (name "TS3") (class "Default")
      (node (ref "CEL3") (pin "6") (pinfunction "CMU6_6") (pintype "bidirectional"))
      (node (ref "R25") (pin "1") (pinfunction "1_1") (pintype "passive"))
    )
    (net (code "74") (name "TS3OUT") (class "Default")
      (node (ref "ANALOG_MUX") (pin "23") (pinfunction "CHAN8_23") (pintype "bidirectional"))
      (node (ref "C12") (pin "2") (pinfunction "2_2") (pintype "passive"))
      (node (ref "R25") (pin "2") (pinfunction "2_2") (pintype "passive"))
    )
    (net (code "75") (name "TS4") (class "Default")
      (node (ref "CEL4") (pin "6") (pinfunction "CMU6_6") (pintype "bidirectional"))
      (node (ref "R29") (pin "1") (pinfunction "1_1") (pintype "passive"))
    )
    (net (code "76") (name "TS4OUT") (class "Default")
      (node (ref "ANALOG_MUX") (pin "19") (pinfunction "CHAN12_19") (pintype "bidirectional"))
      (node (ref "C16") (pin "2") (pinfunction "2_2") (pintype "passive"))
      (node (ref "R29") (pin "2") (pinfunction "2_2") (pintype "passive"))
    )
    (net (code "77") (name "TS_CON") (class "Default")
      (node (ref "C24") (pin "1") (pinfunction "1_1") (pintype "passive"))
      (node (ref "LMT87") (pin "OUT") (pinfunction "OUT_OUT") (pintype "bidirectional"))
      (node (ref "U$1") (pin "A6") (pinfunction "A6_A6") (pintype "bidirectional"))
    )
    (net (code "78") (name "TX") (class "Default")
      (node (ref "U$4") (pin "15") (pinfunction "T1OUT_15") (pintype "output"))
      (node (ref "X2") (pin "3") (pinfunction "3_3") (pintype "passive"))
    )
    (net (code "79") (name "TX1") (class "Default")
      (node (ref "U$1") (pin "TX1") (pinfunction "TX1_TX1") (pintype "bidirectional"))
      (node (ref "U$4") (pin "12") (pinfunction "T1IN_12") (pintype "input"))
    )
    (net (code "80") (name "VS1") (class "Default")
      (node (ref "CEL1") (pin "7") (pinfunction "CMU7_7") (pintype "bidirectional"))
      (node (ref "R13") (pin "1") (pinfunction "1_1") (pintype "passive"))
    )
    (net (code "81") (name "VS2") (class "Default")
      (node (ref "CEL2") (pin "7") (pinfunction "CMU7_7") (pintype "bidirectional"))
      (node (ref "R24") (pin "1") (pinfunction "1_1") (pintype "passive"))
    )
    (net (code "82") (name "VS3") (class "Default")
      (node (ref "CEL3") (pin "7") (pinfunction "CMU7_7") (pintype "bidirectional"))
      (node (ref "R28") (pin "1") (pinfunction "1_1") (pintype "passive"))
    )
    (net (code "83") (name "VS4") (class "Default")
      (node (ref "CEL4") (pin "7") (pinfunction "CMU7_7") (pintype "bidirectional"))
      (node (ref "R32") (pin "1") (pinfunction "1_1") (pintype "passive"))
    )
    (net (code "84") (name "unconnected-(U$1-Pad3V3)") (class "Default")
      (node (ref "U$1") (pin "3V3") (pinfunction "3V3_3V3") (pintype "bidirectional"))
    )
    (net (code "85") (name "unconnected-(U$1-Pad5)") (class "Default")
      (node (ref "U$1") (pin "5") (pinfunction "5_5") (pintype "bidirectional"))
    )
    (net (code "86") (name "unconnected-(U$1-Pad5V)") (class "Default")
      (node (ref "U$1") (pin "5V") (pinfunction "5V_5V") (pintype "bidirectional"))
    )
    (net (code "87") (name "unconnected-(U$1-Pad6)") (class "Default")
      (node (ref "U$1") (pin "6") (pinfunction "6_6") (pintype "bidirectional"))
    )
    (net (code "88") (name "unconnected-(U$1-Pad7)") (class "Default")
      (node (ref "U$1") (pin "7") (pinfunction "7_7") (pintype "bidirectional"))
    )
    (net (code "89") (name "unconnected-(U$1-Pad8)") (class "Default")
      (node (ref "U$1") (pin "8") (pinfunction "8_8") (pintype "bidirectional"))
    )
    (net (code "90") (name "unconnected-(U$1-Pad13)") (class "Default")
      (node (ref "U$1") (pin "13") (pinfunction "13_13") (pintype "bidirectional"))
    )
    (net (code "91") (name "unconnected-(U$1-PadA7)") (class "Default")
      (node (ref "U$1") (pin "A7") (pinfunction "A7_A7") (pintype "bidirectional"))
    )
    (net (code "92") (name "unconnected-(U$1-PadA10)") (class "Default")
      (node (ref "U$1") (pin "A10") (pinfunction "A10_A10") (pintype "bidirectional"))
    )
    (net (code "93") (name "unconnected-(U$1-PadA11)") (class "Default")
      (node (ref "U$1") (pin "A11") (pinfunction "A11_A11") (pintype "bidirectional"))
    )
    (net (code "94") (name "unconnected-(U$1-PadAREF)") (class "Default")
      (node (ref "U$1") (pin "AREF") (pinfunction "AREF_AREF") (pintype "bidirectional"))
    )
    (net (code "95") (name "unconnected-(U$1-PadCANRX)") (class "Default")
      (node (ref "U$1") (pin "CANRX") (pinfunction "CANRX_CANRX") (pintype "bidirectional"))
    )
    (net (code "96") (name "unconnected-(U$1-PadCANTX)") (class "Default")
      (node (ref "U$1") (pin "CANTX") (pinfunction "CANTX_CANTX") (pintype "bidirectional"))
    )
    (net (code "97") (name "unconnected-(U$1-PadDAC0)") (class "Default")
      (node (ref "U$1") (pin "DAC0") (pinfunction "DAC0_DAC0") (pintype "bidirectional"))
    )
    (net (code "98") (name "unconnected-(U$1-PadDAC1)") (class "Default")
      (node (ref "U$1") (pin "DAC1") (pinfunction "DAC1_DAC1") (pintype "bidirectional"))
    )
    (net (code "99") (name "unconnected-(U$1-PadIOREF)") (class "Default")
      (node (ref "U$1") (pin "IOREF") (pinfunction "IOREF_IOREF") (pintype "bidirectional"))
    )
    (net (code "100") (name "unconnected-(U$1-PadNC)") (class "Default")
      (node (ref "U$1") (pin "NC") (pinfunction "NC_NC") (pintype "bidirectional"))
    )
    (net (code "101") (name "unconnected-(U$1-PadRESET)") (class "Default")
      (node (ref "U$1") (pin "RESET") (pinfunction "RESET_RESET") (pintype "bidirectional"))
    )
    (net (code "102") (name "unconnected-(U$1-PadRX0)") (class "Default")
      (node (ref "U$1") (pin "RX0") (pinfunction "RX0_RX0") (pintype "bidirectional"))
    )
    (net (code "103") (name "unconnected-(U$1-PadSCL)") (class "Default")
      (node (ref "U$1") (pin "SCL") (pinfunction "SCL_SCL") (pintype "bidirectional"))
    )
    (net (code "104") (name "unconnected-(U$1-PadSCL1)") (class "Default")
      (node (ref "U$1") (pin "SCL1") (pinfunction "SCL1_SCL1") (pintype "bidirectional"))
    )
    (net (code "105") (name "unconnected-(U$1-PadSDA)") (class "Default")
      (node (ref "U$1") (pin "SDA") (pinfunction "SDA_SDA") (pintype "bidirectional"))
    )
    (net (code "106") (name "unconnected-(U$1-PadSDA1)") (class "Default")
      (node (ref "U$1") (pin "SDA1") (pinfunction "SDA1_SDA1") (pintype "bidirectional"))
    )
    (net (code "107") (name "unconnected-(U$1-PadTX0)") (class "Default")
      (node (ref "U$1") (pin "TX0") (pinfunction "TX0_TX0") (pintype "bidirectional"))
    )
    (net (code "108") (name "unconnected-(U$4A-R2OUT-Pad10)") (class "Default")
      (node (ref "U$4") (pin "10") (pinfunction "R2OUT_10") (pintype "output"))
    )
    (net (code "109") (name "unconnected-(U$4A-T2OUT-Pad8)") (class "Default")
      (node (ref "U$4") (pin "8") (pinfunction "T2OUT_8") (pintype "output"))
    )
    (net (code "110") (name "~{RES_CEL_1&2}") (class "Default")
      (node (ref "R9") (pin "2") (pinfunction "2_2") (pintype "passive"))
      (node (ref "U$1") (pin "4") (pinfunction "4_4") (pintype "bidirectional"))
    )
    (net (code "111") (name "~{RES_CEL_3&4}") (class "Default")
      (node (ref "R5") (pin "2") (pinfunction "2_2") (pintype "passive"))
      (node (ref "U$1") (pin "3") (pinfunction "3_3") (pintype "bidirectional"))
    )
  )
)
